# hhv-dcdarknet-varient-6.net
KiCad netlist of a schematic drawn in EAGLE
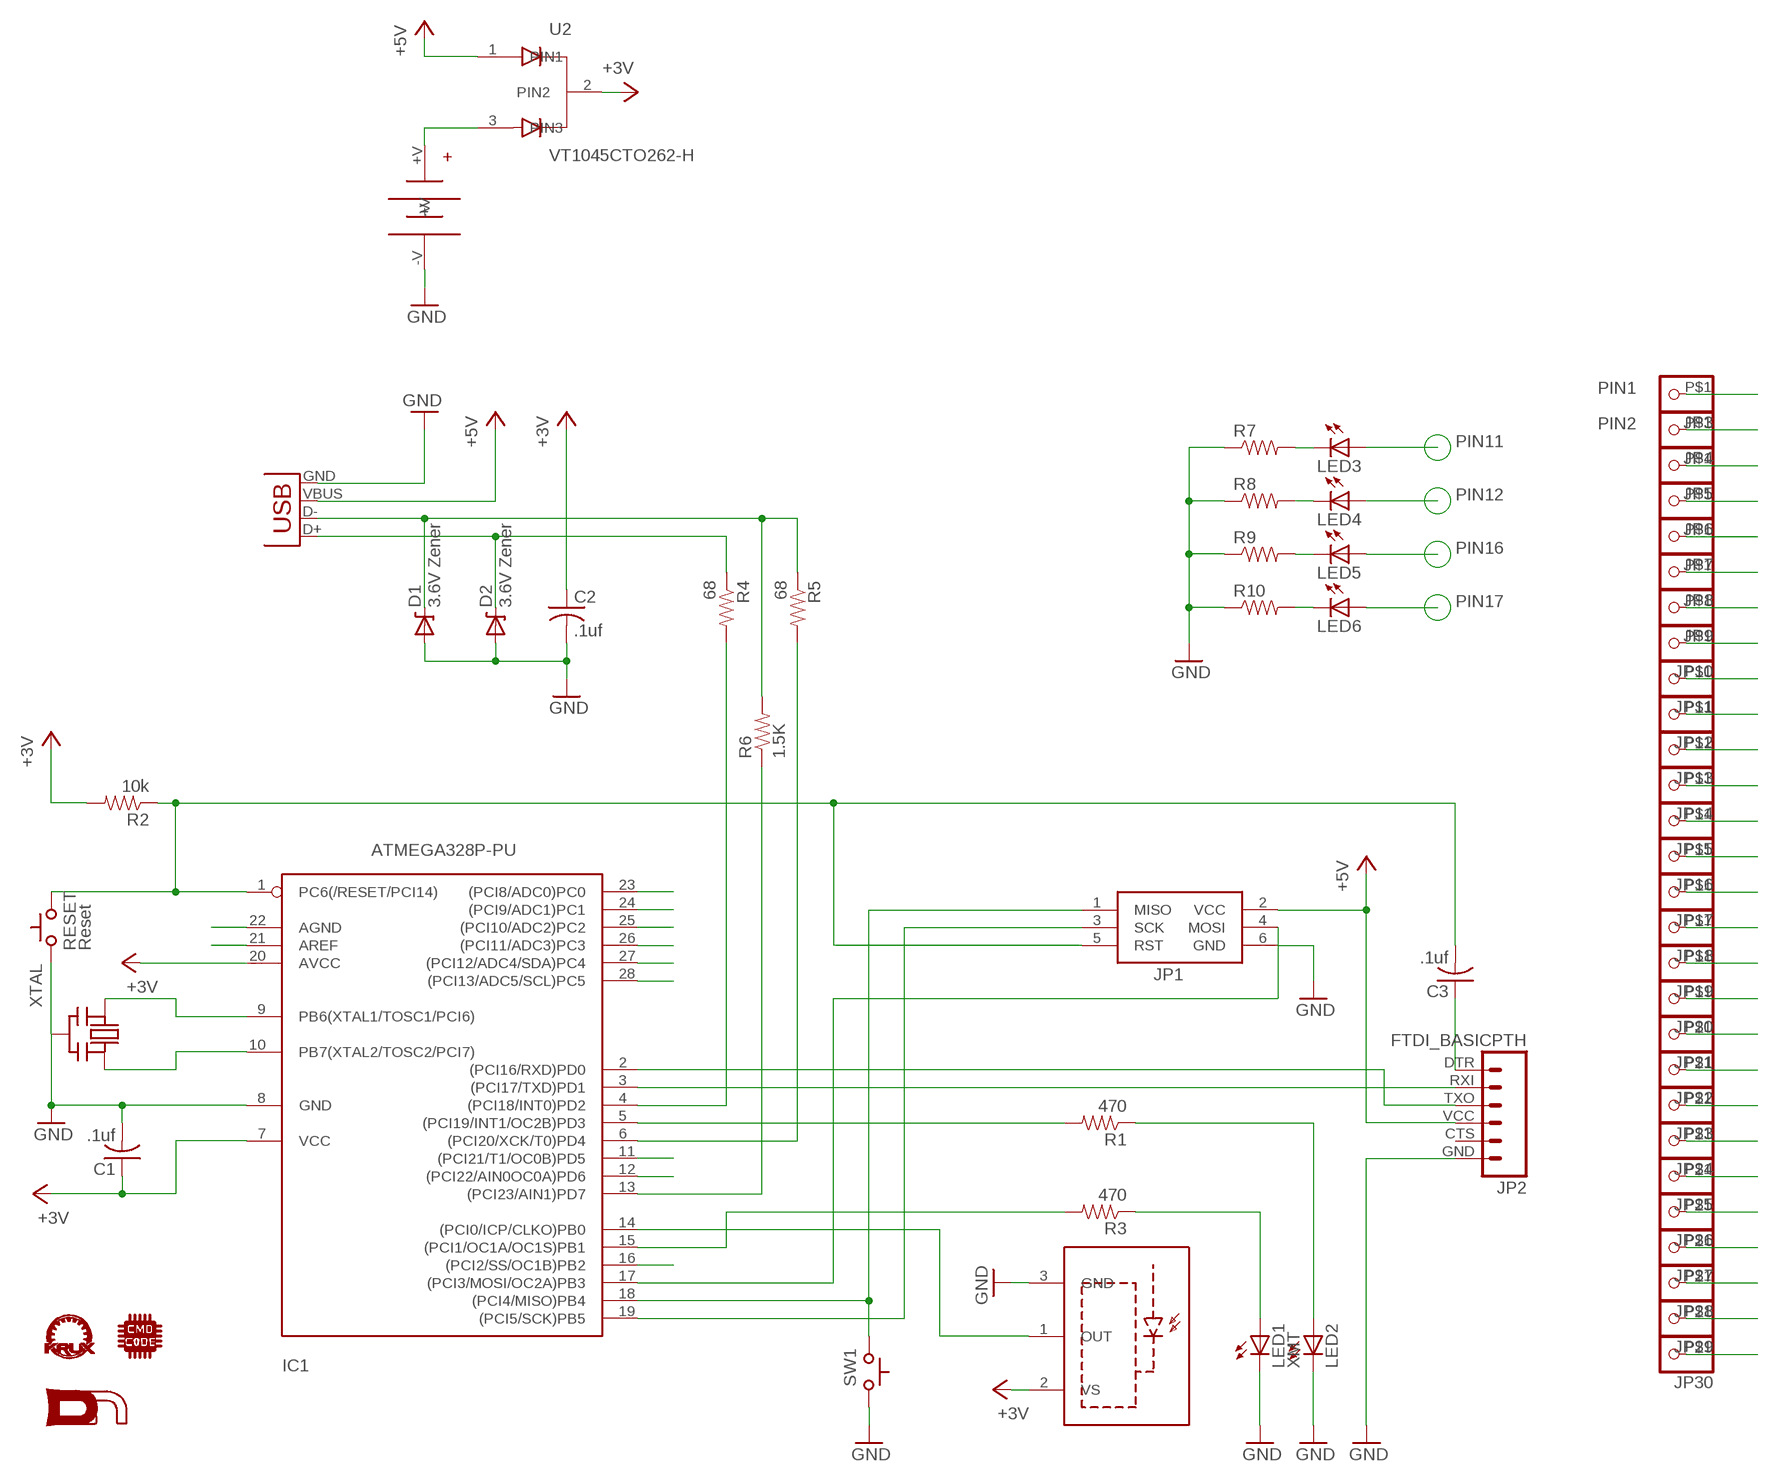
[diagram p0: schematic, sheet 1]

(export (version "E")
  (design (tool "Eeschema 10.0.6"))
  (components
    (comp (ref "C1")
      (value ".1uf")
      (footprint "eagle-import:C025-030X050")
      (libsource (lib "eagle-import") (part "C-US025-030X050"))
    )
    (comp (ref "C2")
      (value ".1uf")
      (footprint "eagle-import:C025-030X050")
      (libsource (lib "eagle-import") (part "C-US025-030X050"))
    )
    (comp (ref "C3")
      (value ".1uf")
      (footprint "eagle-import:C025-030X050")
      (libsource (lib "eagle-import") (part "C-US025-030X050"))
    )
    (comp (ref "D1")
      (value "3.6V Zener")
      (footprint "eagle-import:DIODE-ZENER")
      (libsource (lib "eagle-import") (part "DIODE-ZENERPTH"))
    )
    (comp (ref "D2")
      (value "3.6V Zener")
      (footprint "eagle-import:DIODE-ZENER")
      (libsource (lib "eagle-import") (part "DIODE-ZENERPTH"))
    )
    (comp (ref "IC1")
      (value "ATMEGA328P-PU")
      (footprint "eagle-import:DIL28-3")
      (libsource (lib "eagle-import") (part "ATMEGA168PV-10"))
    )
    (comp (ref "JP1")
      (value "JP1")
      (footprint "eagle-import:AVRISP")
      (libsource (lib "eagle-import") (part "AVRISP-6"))
    )
    (comp (ref "JP2")
      (value "FTDI_BASICPTH")
      (footprint "eagle-import:FTDI_BASIC")
      (libsource (lib "eagle-import") (part "FTDI_BASICPTH"))
    )
    (comp (ref "JP3")
      (value "PINHD-1X11X1_SQUARE")
      (footprint "eagle-import:1X1-SMALL_CUT")
      (libsource (lib "eagle-import") (part "PINHD-1X11X1_SQUARE"))
    )
    (comp (ref "JP4")
      (value "PINHD-1X11X1_SQUARE")
      (footprint "eagle-import:1X1-SMALL_CUT")
      (libsource (lib "eagle-import") (part "PINHD-1X11X1_SQUARE"))
    )
    (comp (ref "JP5")
      (value "PINHD-1X11X1_SQUARE")
      (footprint "eagle-import:1X1-SMALL_CUT")
      (libsource (lib "eagle-import") (part "PINHD-1X11X1_SQUARE"))
    )
    (comp (ref "JP6")
      (value "PINHD-1X11X1_SQUARE")
      (footprint "eagle-import:1X1-SMALL_CUT")
      (libsource (lib "eagle-import") (part "PINHD-1X11X1_SQUARE"))
    )
    (comp (ref "JP7")
      (value "PINHD-1X11X1_SQUARE")
      (footprint "eagle-import:1X1-SMALL_CUT")
      (libsource (lib "eagle-import") (part "PINHD-1X11X1_SQUARE"))
    )
    (comp (ref "JP8")
      (value "PINHD-1X11X1_SQUARE")
      (footprint "eagle-import:1X1-SMALL_CUT")
      (libsource (lib "eagle-import") (part "PINHD-1X11X1_SQUARE"))
    )
    (comp (ref "JP9")
      (value "PINHD-1X11X1_SQUARE")
      (footprint "eagle-import:1X1-SMALL_CUT")
      (libsource (lib "eagle-import") (part "PINHD-1X11X1_SQUARE"))
    )
    (comp (ref "JP10")
      (value "PINHD-1X11X1_SQUARE")
      (footprint "eagle-import:1X1-SMALL_CUT")
      (libsource (lib "eagle-import") (part "PINHD-1X11X1_SQUARE"))
    )
    (comp (ref "JP11")
      (value "PINHD-1X11X1_SQUARE")
      (footprint "eagle-import:1X1-SMALL_CUT")
      (libsource (lib "eagle-import") (part "PINHD-1X11X1_SQUARE"))
    )
    (comp (ref "JP12")
      (value "PINHD-1X11X1_SQUARE")
      (footprint "eagle-import:1X1-SMALL_CUT")
      (libsource (lib "eagle-import") (part "PINHD-1X11X1_SQUARE"))
    )
    (comp (ref "JP13")
      (value "PINHD-1X11X1_SQUARE")
      (footprint "eagle-import:1X1-SMALL_CUT")
      (libsource (lib "eagle-import") (part "PINHD-1X11X1_SQUARE"))
    )
    (comp (ref "JP14")
      (value "PINHD-1X11X1_SQUARE")
      (footprint "eagle-import:1X1-SMALL_CUT")
      (libsource (lib "eagle-import") (part "PINHD-1X11X1_SQUARE"))
    )
    (comp (ref "JP15")
      (value "PINHD-1X11X1_SQUARE")
      (footprint "eagle-import:1X1-SMALL_CUT")
      (libsource (lib "eagle-import") (part "PINHD-1X11X1_SQUARE"))
    )
    (comp (ref "JP16")
      (value "PINHD-1X11X1_SQUARE")
      (footprint "eagle-import:1X1-SMALL_CUT")
      (libsource (lib "eagle-import") (part "PINHD-1X11X1_SQUARE"))
    )
    (comp (ref "JP17")
      (value "PINHD-1X11X1_SQUARE")
      (footprint "eagle-import:1X1-SMALL_CUT")
      (libsource (lib "eagle-import") (part "PINHD-1X11X1_SQUARE"))
    )
    (comp (ref "JP18")
      (value "PINHD-1X11X1_SQUARE")
      (footprint "eagle-import:1X1-SMALL_CUT")
      (libsource (lib "eagle-import") (part "PINHD-1X11X1_SQUARE"))
    )
    (comp (ref "JP19")
      (value "PINHD-1X11X1_SQUARE")
      (footprint "eagle-import:1X1-SMALL_CUT")
      (libsource (lib "eagle-import") (part "PINHD-1X11X1_SQUARE"))
    )
    (comp (ref "JP20")
      (value "PINHD-1X11X1_SQUARE")
      (footprint "eagle-import:1X1-SMALL_CUT")
      (libsource (lib "eagle-import") (part "PINHD-1X11X1_SQUARE"))
    )
    (comp (ref "JP21")
      (value "PINHD-1X11X1_SQUARE")
      (footprint "eagle-import:1X1-SMALL_CUT")
      (libsource (lib "eagle-import") (part "PINHD-1X11X1_SQUARE"))
    )
    (comp (ref "JP22")
      (value "PINHD-1X11X1_SQUARE")
      (footprint "eagle-import:1X1-SMALL_CUT")
      (libsource (lib "eagle-import") (part "PINHD-1X11X1_SQUARE"))
    )
    (comp (ref "JP23")
      (value "PINHD-1X11X1_SQUARE")
      (footprint "eagle-import:1X1-SMALL_CUT")
      (libsource (lib "eagle-import") (part "PINHD-1X11X1_SQUARE"))
    )
    (comp (ref "JP24")
      (value "PINHD-1X11X1-SMALL")
      (footprint "eagle-import:1X1-SMALL")
      (libsource (lib "eagle-import") (part "PINHD-1X11X1-SMALL"))
    )
    (comp (ref "JP25")
      (value "PINHD-1X11X1_SQUARE")
      (footprint "eagle-import:1X1-SMALL_CUT")
      (libsource (lib "eagle-import") (part "PINHD-1X11X1_SQUARE"))
    )
    (comp (ref "JP26")
      (value "PINHD-1X11X1_SQUARE")
      (footprint "eagle-import:1X1-SMALL_CUT")
      (libsource (lib "eagle-import") (part "PINHD-1X11X1_SQUARE"))
    )
    (comp (ref "JP27")
      (value "PINHD-1X11X1-SMALL")
      (footprint "eagle-import:1X1-SMALL")
      (libsource (lib "eagle-import") (part "PINHD-1X11X1-SMALL"))
    )
    (comp (ref "JP28")
      (value "PINHD-1X11X1_SQUARE")
      (footprint "eagle-import:1X1-SMALL_CUT")
      (libsource (lib "eagle-import") (part "PINHD-1X11X1_SQUARE"))
    )
    (comp (ref "JP29")
      (value "PINHD-1X11X1_SQUARE")
      (footprint "eagle-import:1X1-SMALL_CUT")
      (libsource (lib "eagle-import") (part "PINHD-1X11X1_SQUARE"))
    )
    (comp (ref "JP30")
      (value "PINHD-1X11X1-SMALL")
      (footprint "eagle-import:1X1-SMALL")
      (libsource (lib "eagle-import") (part "PINHD-1X11X1-SMALL"))
    )
    (comp (ref "LED1")
      (value "XMT")
      (footprint "eagle-import:LED5MM-FLAT")
      (libsource (lib "eagle-import") (part "LED5MM-FLAT"))
    )
    (comp (ref "LED2")
      (value "LED5MM-FLAT")
      (footprint "eagle-import:LED5MM-FLAT")
      (libsource (lib "eagle-import") (part "LED5MM-FLAT"))
    )
    (comp (ref "LED3")
      (value "LED1206")
      (footprint "eagle-import:LED-1206")
      (libsource (lib "eagle-import") (part "SparkFun_LED1206"))
    )
    (comp (ref "LED4")
      (value "LED1206")
      (footprint "eagle-import:LED-1206")
      (libsource (lib "eagle-import") (part "SparkFun_LED1206"))
    )
    (comp (ref "LED5")
      (value "LED1206")
      (footprint "eagle-import:LED-1206")
      (libsource (lib "eagle-import") (part "SparkFun_LED1206"))
    )
    (comp (ref "LED6")
      (value "LED1206")
      (footprint "eagle-import:LED-1206")
      (libsource (lib "eagle-import") (part "SparkFun_LED1206"))
    )
    (comp (ref "R1")
      (value "470")
      (footprint "eagle-import:AXIAL-0.3")
      (libsource (lib "eagle-import") (part "RESISTORAXIAL-0.3"))
    )
    (comp (ref "R2")
      (value "10k")
      (footprint "eagle-import:AXIAL-0.3")
      (libsource (lib "eagle-import") (part "RESISTORAXIAL-0.3"))
    )
    (comp (ref "R3")
      (value "470")
      (footprint "eagle-import:AXIAL-0.3")
      (libsource (lib "eagle-import") (part "RESISTORAXIAL-0.3"))
    )
    (comp (ref "R4")
      (value "68")
      (footprint "eagle-import:AXIAL-0.3")
      (libsource (lib "eagle-import") (part "RESISTORAXIAL-0.3"))
    )
    (comp (ref "R5")
      (value "68")
      (footprint "eagle-import:AXIAL-0.3")
      (libsource (lib "eagle-import") (part "RESISTORAXIAL-0.3"))
    )
    (comp (ref "R6")
      (value "1.5K")
      (footprint "eagle-import:AXIAL-0.3")
      (libsource (lib "eagle-import") (part "RESISTORAXIAL-0.3"))
    )
    (comp (ref "R7")
      (value "RESISTOR1206")
      (footprint "eagle-import:1206")
      (libsource (lib "eagle-import") (part "SparkFun_RESISTOR1206"))
    )
    (comp (ref "R8")
      (value "RESISTOR1206")
      (footprint "eagle-import:1206")
      (libsource (lib "eagle-import") (part "SparkFun_RESISTOR1206"))
    )
    (comp (ref "R9")
      (value "RESISTOR1206")
      (footprint "eagle-import:1206")
      (libsource (lib "eagle-import") (part "SparkFun_RESISTOR1206"))
    )
    (comp (ref "R10")
      (value "RESISTOR1206")
      (footprint "eagle-import:1206")
      (libsource (lib "eagle-import") (part "SparkFun_RESISTOR1206"))
    )
    (comp (ref "RESET")
      (value "Reset")
      (footprint "eagle-import:TACTILE-2PIN")
      (libsource (lib "eagle-import") (part "SWITCH_TACTILETACTILE-2PIN"))
    )
    (comp (ref "SW1")
      (value "SWITCH_TACTILETACTILE-2PIN")
      (footprint "eagle-import:TACTILE-2PIN")
      (libsource (lib "eagle-import") (part "SWITCH_TACTILETACTILE-2PIN"))
    )
    (comp (ref "U$1")
      (value "DN_LOGO")
      (footprint "eagle-import:DN_LOGO")
      (libsource (lib "eagle-import") (part "DN_LOGO"))
    )
    (comp (ref "U$2")
      (value "CMDC0DE_LOGO")
      (footprint "eagle-import:CMDC0DE")
      (libsource (lib "eagle-import") (part "CMDC0DE_LOGO"))
    )
    (comp (ref "U$3")
      (value "KRUX_LOGO")
      (footprint "eagle-import:KRUX_LOGO")
      (libsource (lib "eagle-import") (part "KRUX_LOGO"))
    )
    (comp (ref "U$5")
      (value "12BH423-GR3-CELL_NOBORDER")
      (footprint "eagle-import:3-AAA-CELL_NOBORDER")
      (libsource (lib "eagle-import") (part "12BH423-GR3-CELL_NOBORDER"))
    )
    (comp (ref "U1")
      (value "RCV")
      (footprint "eagle-import:IR-MODULE")
      (libsource (lib "eagle-import") (part "SOP22"))
    )
    (comp (ref "U2")
      (value "VT1045CTO262-H")
      (footprint "eagle-import:TO262-H")
      (libsource (lib "eagle-import") (part "VT1045CTO262-H"))
    )
    (comp (ref "X2")
      (value "USB")
      (footprint "eagle-import:USB-B-PTH")
      (libsource (lib "eagle-import") (part "USBPTH"))
    )
    (comp (ref "XTAL")
      (value "CERMOSCILL-THM")
      (footprint "eagle-import:CERM_OSC")
      (libsource (lib "eagle-import") (part "CERMOSCILL-THM"))
    )
  )
  (nets
    (net (code "1") (name "+3V") (class "Default")
      (node (ref "C1") (pin "1") (pinfunction "1_1") (pintype "passive"))
      (node (ref "C2") (pin "1") (pinfunction "1_1") (pintype "passive"))
      (node (ref "IC1") (pin "20") (pinfunction "AVCC_20") (pintype "bidirectional"))
      (node (ref "IC1") (pin "7") (pinfunction "VCC_7") (pintype "bidirectional"))
      (node (ref "JP22") (pin "P$1") (pinfunction "1_P$1") (pintype "passive"))
      (node (ref "JP9") (pin "P$1") (pinfunction "1_P$1") (pintype "passive"))
      (node (ref "R2") (pin "P$2") (pinfunction "2_P$2") (pintype "passive"))
      (node (ref "U1") (pin "2") (pinfunction "VS_2") (pintype "bidirectional"))
      (node (ref "U2") (pin "2") (pinfunction "PIN2_2") (pintype "bidirectional"))
    )
    (net (code "2") (name "+5V") (class "Default")
      (node (ref "JP1") (pin "2") (pinfunction "VCC_2") (pintype "power_in"))
      (node (ref "JP2") (pin "VCC") (pinfunction "4_VCC") (pintype "passive"))
      (node (ref "U2") (pin "1") (pinfunction "PIN1_1") (pintype "bidirectional"))
      (node (ref "X2") (pin "VBUS") (pinfunction "VBUS_VBUS") (pintype "bidirectional"))
    )
    (net (code "3") (name "/PIN1") (class "Default")
      (node (ref "C3") (pin "2") (pinfunction "2_2") (pintype "passive"))
      (node (ref "IC1") (pin "1") (pinfunction "PC6(/RESET/PCI14)_1") (pintype "bidirectional"))
      (node (ref "JP1") (pin "5") (pinfunction "RST_5") (pintype "output"))
      (node (ref "JP3") (pin "P$1") (pinfunction "1_P$1") (pintype "passive"))
      (node (ref "R2") (pin "P$1") (pinfunction "1_P$1") (pintype "passive"))
      (node (ref "RESET") (pin "P$1") (pinfunction "A_P$1") (pintype "passive"))
    )
    (net (code "4") (name "/PIN2") (class "Default")
      (node (ref "IC1") (pin "2") (pinfunction "(PCI16/RXD)PD0_2") (pintype "bidirectional"))
      (node (ref "JP2") (pin "TXO") (pinfunction "3_TXO") (pintype "passive"))
      (node (ref "JP4") (pin "P$1") (pinfunction "1_P$1") (pintype "passive"))
    )
    (net (code "5") (name "/PIN3") (class "Default")
      (node (ref "IC1") (pin "3") (pinfunction "(PCI17/TXD)PD1_3") (pintype "bidirectional"))
      (node (ref "JP2") (pin "RXI") (pinfunction "2_RXI") (pintype "passive"))
      (node (ref "JP5") (pin "P$1") (pinfunction "1_P$1") (pintype "passive"))
    )
    (net (code "6") (name "/PIN4") (class "Default")
      (node (ref "IC1") (pin "4") (pinfunction "(PCI18/INT0)PD2_4") (pintype "bidirectional"))
      (node (ref "JP6") (pin "P$1") (pinfunction "1_P$1") (pintype "passive"))
      (node (ref "R4") (pin "P$2") (pinfunction "2_P$2") (pintype "passive"))
    )
    (net (code "7") (name "/PIN5") (class "Default")
      (node (ref "IC1") (pin "5") (pinfunction "(PCI19/INT1/OC2B)PD3_5") (pintype "bidirectional"))
      (node (ref "JP7") (pin "P$1") (pinfunction "1_P$1") (pintype "passive"))
      (node (ref "R1") (pin "P$2") (pinfunction "2_P$2") (pintype "passive"))
    )
    (net (code "8") (name "/PIN6") (class "Default")
      (node (ref "IC1") (pin "6") (pinfunction "(PCI20/XCK/T0)PD4_6") (pintype "bidirectional"))
      (node (ref "JP8") (pin "P$1") (pinfunction "1_P$1") (pintype "passive"))
      (node (ref "R5") (pin "P$2") (pinfunction "2_P$2") (pintype "passive"))
    )
    (net (code "9") (name "/PIN9") (class "Default")
      (node (ref "IC1") (pin "9") (pinfunction "PB6(XTAL1/TOSC1/PCI6)_9") (pintype "bidirectional"))
      (node (ref "JP11") (pin "P$1") (pinfunction "1_P$1") (pintype "passive"))
      (node (ref "XTAL") (pin "P$1") (pinfunction "IN_P$1") (pintype "bidirectional"))
    )
    (net (code "10") (name "/PIN10") (class "Default")
      (node (ref "IC1") (pin "10") (pinfunction "PB7(XTAL2/TOSC2/PCI7)_10") (pintype "bidirectional"))
      (node (ref "JP12") (pin "P$1") (pinfunction "1_P$1") (pintype "passive"))
      (node (ref "XTAL") (pin "P$3") (pinfunction "OUT_P$3") (pintype "bidirectional"))
    )
    (net (code "11") (name "/PIN11") (class "Default")
      (node (ref "IC1") (pin "11") (pinfunction "(PCI21/T1/OC0B)PD5_11") (pintype "bidirectional"))
      (node (ref "JP13") (pin "P$1") (pinfunction "1_P$1") (pintype "passive"))
      (node (ref "LED3") (pin "A") (pinfunction "A_A") (pintype "passive"))
    )
    (net (code "12") (name "/PIN12") (class "Default")
      (node (ref "IC1") (pin "12") (pinfunction "(PCI22/AIN0OC0A)PD6_12") (pintype "bidirectional"))
      (node (ref "JP14") (pin "P$1") (pinfunction "1_P$1") (pintype "passive"))
      (node (ref "LED4") (pin "A") (pinfunction "A_A") (pintype "passive"))
    )
    (net (code "13") (name "/PIN13") (class "Default")
      (node (ref "IC1") (pin "13") (pinfunction "(PCI23/AIN1)PD7_13") (pintype "bidirectional"))
      (node (ref "JP15") (pin "P$1") (pinfunction "1_P$1") (pintype "passive"))
      (node (ref "R6") (pin "P$1") (pinfunction "1_P$1") (pintype "passive"))
    )
    (net (code "14") (name "/PIN14") (class "Default")
      (node (ref "IC1") (pin "14") (pinfunction "(PCI0/ICP/CLKO)PB0_14") (pintype "bidirectional"))
      (node (ref "JP16") (pin "P$1") (pinfunction "1_P$1") (pintype "passive"))
      (node (ref "U1") (pin "1") (pinfunction "OUT_1") (pintype "bidirectional"))
    )
    (net (code "15") (name "/PIN15") (class "Default")
      (node (ref "IC1") (pin "15") (pinfunction "(PCI1/OC1A/OC1S)PB1_15") (pintype "bidirectional"))
      (node (ref "JP17") (pin "P$1") (pinfunction "1_P$1") (pintype "passive"))
      (node (ref "R3") (pin "P$2") (pinfunction "2_P$2") (pintype "passive"))
    )
    (net (code "16") (name "/PIN16") (class "Default")
      (node (ref "IC1") (pin "16") (pinfunction "(PCI2/SS/OC1B)PB2_16") (pintype "bidirectional"))
      (node (ref "JP18") (pin "P$1") (pinfunction "1_P$1") (pintype "passive"))
      (node (ref "LED5") (pin "A") (pinfunction "A_A") (pintype "passive"))
    )
    (net (code "17") (name "/PIN17") (class "Default")
      (node (ref "IC1") (pin "17") (pinfunction "(PCI3/MOSI/OC2A)PB3_17") (pintype "bidirectional"))
      (node (ref "JP1") (pin "4") (pinfunction "MOSI_4") (pintype "output"))
      (node (ref "JP19") (pin "P$1") (pinfunction "1_P$1") (pintype "passive"))
      (node (ref "LED6") (pin "A") (pinfunction "A_A") (pintype "passive"))
    )
    (net (code "18") (name "/PIN18") (class "Default")
      (node (ref "IC1") (pin "18") (pinfunction "(PCI4/MISO)PB4_18") (pintype "bidirectional"))
      (node (ref "JP1") (pin "1") (pinfunction "MISO_1") (pintype "input"))
      (node (ref "JP20") (pin "P$1") (pinfunction "1_P$1") (pintype "passive"))
      (node (ref "SW1") (pin "P$2") (pinfunction "C_P$2") (pintype "passive"))
    )
    (net (code "19") (name "/PIN19") (class "Default")
      (node (ref "IC1") (pin "19") (pinfunction "(PCI5/SCK)PB5_19") (pintype "bidirectional"))
      (node (ref "JP1") (pin "3") (pinfunction "SCK_3") (pintype "output"))
      (node (ref "JP21") (pin "P$1") (pinfunction "1_P$1") (pintype "passive"))
    )
    (net (code "20") (name "/PIN21") (class "Default")
      (node (ref "IC1") (pin "21") (pinfunction "AREF_21") (pintype "bidirectional"))
      (node (ref "JP23") (pin "P$1") (pinfunction "1_P$1") (pintype "passive"))
    )
    (net (code "21") (name "/PIN22") (class "Default")
      (node (ref "IC1") (pin "22") (pinfunction "AGND_22") (pintype "bidirectional"))
      (node (ref "JP24") (pin "P$1") (pinfunction "1_P$1") (pintype "passive"))
    )
    (net (code "22") (name "/PIN23") (class "Default")
      (node (ref "IC1") (pin "23") (pinfunction "(PCI8/ADC0)PC0_23") (pintype "bidirectional"))
      (node (ref "JP25") (pin "P$1") (pinfunction "1_P$1") (pintype "passive"))
    )
    (net (code "23") (name "/PIN24") (class "Default")
      (node (ref "IC1") (pin "24") (pinfunction "(PCI9/ADC1)PC1_24") (pintype "bidirectional"))
      (node (ref "JP26") (pin "P$1") (pinfunction "1_P$1") (pintype "passive"))
    )
    (net (code "24") (name "/PIN25") (class "Default")
      (node (ref "IC1") (pin "25") (pinfunction "(PCI10/ADC2)PC2_25") (pintype "bidirectional"))
      (node (ref "JP27") (pin "P$1") (pinfunction "1_P$1") (pintype "passive"))
    )
    (net (code "25") (name "/PIN26") (class "Default")
      (node (ref "IC1") (pin "26") (pinfunction "(PCI11/ADC3)PC3_26") (pintype "bidirectional"))
      (node (ref "JP28") (pin "P$1") (pinfunction "1_P$1") (pintype "passive"))
    )
    (net (code "26") (name "/PIN27") (class "Default")
      (node (ref "IC1") (pin "27") (pinfunction "(PCI12/ADC4/SDA)PC4_27") (pintype "bidirectional"))
      (node (ref "JP29") (pin "P$1") (pinfunction "1_P$1") (pintype "passive"))
    )
    (net (code "27") (name "/PIN28") (class "Default")
      (node (ref "IC1") (pin "28") (pinfunction "(PCI13/ADC5/SCL)PC5_28") (pintype "bidirectional"))
      (node (ref "JP30") (pin "P$1") (pinfunction "1_P$1") (pintype "passive"))
    )
    (net (code "28") (name "GND") (class "Default")
      (node (ref "C1") (pin "2") (pinfunction "2_2") (pintype "passive"))
      (node (ref "C2") (pin "2") (pinfunction "2_2") (pintype "passive"))
      (node (ref "D1") (pin "P$2") (pinfunction "A_P$2") (pintype "passive"))
      (node (ref "D2") (pin "P$2") (pinfunction "A_P$2") (pintype "passive"))
      (node (ref "IC1") (pin "8") (pinfunction "GND_8") (pintype "bidirectional"))
      (node (ref "JP1") (pin "6") (pinfunction "GND_6") (pintype "power_in"))
      (node (ref "JP10") (pin "P$1") (pinfunction "1_P$1") (pintype "passive"))
      (node (ref "JP2") (pin "GND") (pinfunction "6_GND") (pintype "passive"))
      (node (ref "LED1") (pin "K") (pinfunction "C_K") (pintype "passive"))
      (node (ref "LED2") (pin "K") (pinfunction "C_K") (pintype "passive"))
      (node (ref "R10") (pin "1") (pinfunction "1_1") (pintype "passive"))
      (node (ref "R7") (pin "1") (pinfunction "1_1") (pintype "passive"))
      (node (ref "R8") (pin "1") (pinfunction "1_1") (pintype "passive"))
      (node (ref "R9") (pin "1") (pinfunction "1_1") (pintype "passive"))
      (node (ref "RESET") (pin "P$2") (pinfunction "C_P$2") (pintype "passive"))
      (node (ref "SW1") (pin "P$1") (pinfunction "A_P$1") (pintype "passive"))
      (node (ref "U$5") (pin "-V") (pinfunction "-V_-V") (pintype "bidirectional"))
      (node (ref "U1") (pin "3") (pinfunction "GND_3") (pintype "bidirectional"))
      (node (ref "X2") (pin "GND") (pinfunction "GND_GND") (pintype "bidirectional"))
      (node (ref "XTAL") (pin "P$2") (pinfunction "GND_P$2") (pintype "bidirectional"))
    )
    (net (code "29") (name "Net-(D1-C)") (class "Default")
      (node (ref "D1") (pin "P$1") (pinfunction "C_P$1") (pintype "passive"))
      (node (ref "R5") (pin "P$1") (pinfunction "1_P$1") (pintype "passive"))
      (node (ref "R6") (pin "P$2") (pinfunction "2_P$2") (pintype "passive"))
      (node (ref "X2") (pin "D-") (pinfunction "D-_D-") (pintype "bidirectional"))
    )
    (net (code "30") (name "Net-(D2-C)") (class "Default")
      (node (ref "D2") (pin "P$1") (pinfunction "C_P$1") (pintype "passive"))
      (node (ref "R4") (pin "P$1") (pinfunction "1_P$1") (pintype "passive"))
      (node (ref "X2") (pin "D+") (pinfunction "D+_D+") (pintype "bidirectional"))
    )
    (net (code "31") (name "Net-(JP2-1)") (class "Default")
      (node (ref "C3") (pin "1") (pinfunction "1_1") (pintype "passive"))
      (node (ref "JP2") (pin "DTR") (pinfunction "1_DTR") (pintype "passive"))
    )
    (net (code "32") (name "Net-(LED3-PadC)") (class "Default")
      (node (ref "LED3") (pin "C") (pinfunction "C_C") (pintype "passive"))
      (node (ref "R7") (pin "2") (pinfunction "2_2") (pintype "passive"))
    )
    (net (code "33") (name "Net-(LED4-PadC)") (class "Default")
      (node (ref "LED4") (pin "C") (pinfunction "C_C") (pintype "passive"))
      (node (ref "R8") (pin "2") (pinfunction "2_2") (pintype "passive"))
    )
    (net (code "34") (name "Net-(LED5-PadC)") (class "Default")
      (node (ref "LED5") (pin "C") (pinfunction "C_C") (pintype "passive"))
      (node (ref "R9") (pin "2") (pinfunction "2_2") (pintype "passive"))
    )
    (net (code "35") (name "Net-(LED6-PadC)") (class "Default")
      (node (ref "LED6") (pin "C") (pinfunction "C_C") (pintype "passive"))
      (node (ref "R10") (pin "2") (pinfunction "2_2") (pintype "passive"))
    )
    (net (code "36") (name "Net-(R1-1)") (class "Default")
      (node (ref "LED2") (pin "A") (pinfunction "A_A") (pintype "passive"))
      (node (ref "R1") (pin "P$1") (pinfunction "1_P$1") (pintype "passive"))
    )
    (net (code "37") (name "Net-(R3-1)") (class "Default")
      (node (ref "LED1") (pin "A") (pinfunction "A_A") (pintype "passive"))
      (node (ref "R3") (pin "P$1") (pinfunction "1_P$1") (pintype "passive"))
    )
    (net (code "38") (name "Net-(U2-PIN3)") (class "Default")
      (node (ref "U$5") (pin "+V") (pinfunction "+V_+V") (pintype "bidirectional"))
      (node (ref "U2") (pin "3") (pinfunction "PIN3_3") (pintype "bidirectional"))
    )
    (net (code "39") (name "unconnected-(JP2-5-PadCTS)") (class "Default")
      (node (ref "JP2") (pin "CTS") (pinfunction "5_CTS") (pintype "passive"))
    )
  )
)
